# fab-slider-shield-v2_controls-only.net
KiCad netlist of a schematic drawn in EAGLE
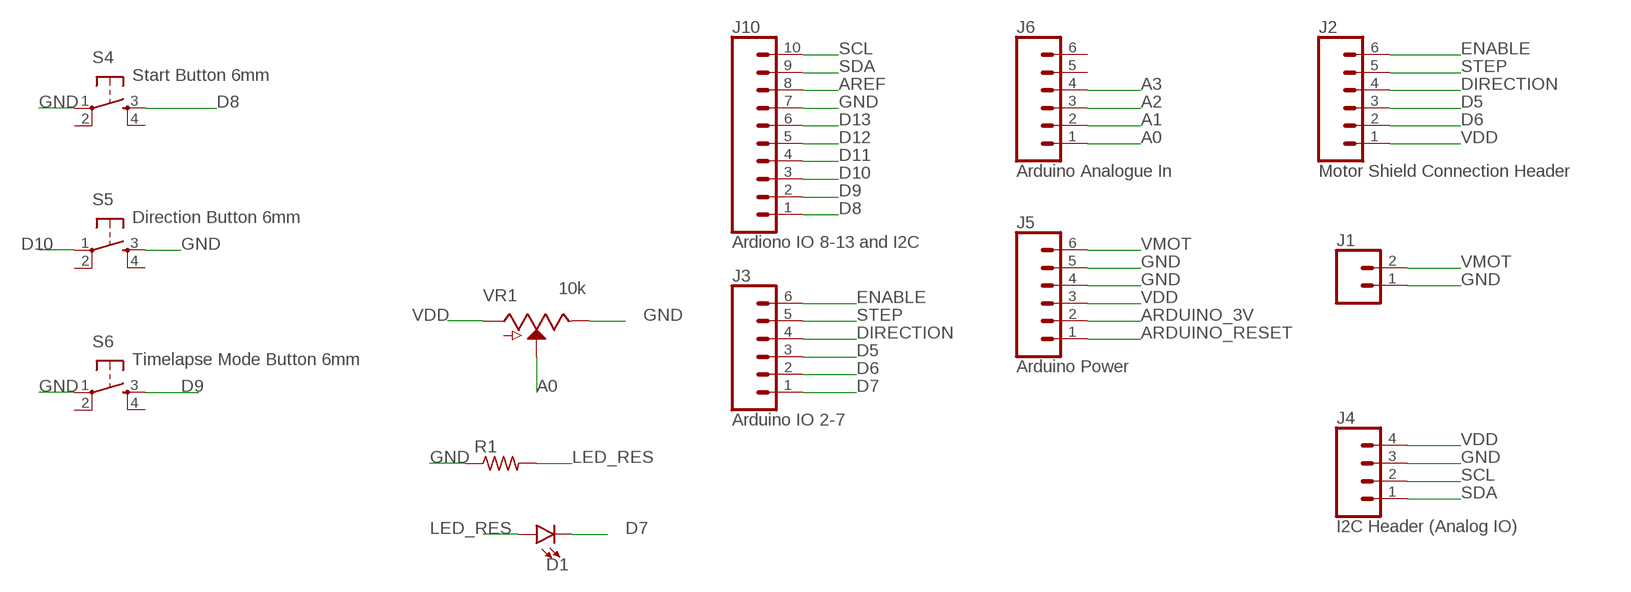
[diagram p0: schematic, sheet 1]

(export (version "E")
  (design (tool "Eeschema 10.0.6"))
  (components
    (comp (ref "D1")
      (value "LED1206")
      (footprint "eagle-import:LED-1206")
      (libsource (lib "eagle-import") (part "LED1206"))
    )
    (comp (ref "J1")
      (value "CONN_02PTH3")
      (footprint "eagle-import:1X02_LONGPADS")
      (libsource (lib "eagle-import") (part "CONN_02PTH3"))
    )
    (comp (ref "J2")
      (value "Motor Shield Connection Header")
      (footprint "eagle-import:1X06_LONGPADS")
      (libsource (lib "eagle-import") (part "CONN_06LONGPADS"))
    )
    (comp (ref "J3")
      (value "Arduino IO 2-7")
      (footprint "eagle-import:1X06_NO_SILK")
      (libsource (lib "eagle-import") (part "CONN_06NO_SILK_FEMALE_PTH"))
    )
    (comp (ref "J4")
      (value "I2C Header (Analog IO)")
      (footprint "eagle-import:1X04")
      (libsource (lib "eagle-import") (part "CONN_04"))
    )
    (comp (ref "J5")
      (value "Arduino Power")
      (footprint "eagle-import:1X06_NO_SILK")
      (libsource (lib "eagle-import") (part "CONN_06NO_SILK_FEMALE_PTH"))
    )
    (comp (ref "J6")
      (value "Arduino Analogue In")
      (footprint "eagle-import:1X06_NO_SILK")
      (libsource (lib "eagle-import") (part "CONN_06NO_SILK_FEMALE_PTH"))
    )
    (comp (ref "J10")
      (value "Ardiono IO 8-13 and I2C")
      (footprint "eagle-import:1X10_NO_SILK")
      (libsource (lib "eagle-import") (part "CONN_10NO_SILK_PTH_FEMALE"))
    )
    (comp (ref "R1")
      (value "RES-US1206FAB")
      (footprint "eagle-import:R1206FAB")
      (libsource (lib "eagle-import") (part "RES-US1206FAB"))
    )
    (comp (ref "S4")
      (value "Start Button 6mm")
      (footprint "eagle-import:6MM_SWITCH")
      (libsource (lib "eagle-import") (part "6MM_SWITCH6MM_SWITCH"))
    )
    (comp (ref "S5")
      (value "Direction Button 6mm")
      (footprint "eagle-import:6MM_SWITCH")
      (libsource (lib "eagle-import") (part "6MM_SWITCH6MM_SWITCH"))
    )
    (comp (ref "S6")
      (value "Timelapse Mode Button 6mm")
      (footprint "eagle-import:6MM_SWITCH")
      (libsource (lib "eagle-import") (part "6MM_SWITCH6MM_SWITCH"))
    )
    (comp (ref "VR1")
      (value "10k")
      (footprint "eagle-import:POT-PTH-ALPS")
      (libsource (lib "eagle-import") (part "POTENTIOMETER-PTH-9MM-1/20W-20%"))
    )
  )
  (nets
    (net (code "1") (name "/A0") (class "Default")
      (node (ref "J6") (pin "1") (pinfunction "1_1") (pintype "passive"))
      (node (ref "VR1") (pin "P$2") (pinfunction "S_P$2") (pintype "passive"))
    )
    (net (code "2") (name "/A1") (class "Default")
      (node (ref "J6") (pin "2") (pinfunction "2_2") (pintype "passive"))
    )
    (net (code "3") (name "/A2") (class "Default")
      (node (ref "J6") (pin "3") (pinfunction "3_3") (pintype "passive"))
    )
    (net (code "4") (name "/A3") (class "Default")
      (node (ref "J6") (pin "4") (pinfunction "4_4") (pintype "passive"))
    )
    (net (code "5") (name "/ARDUINO_3V") (class "Default")
      (node (ref "J5") (pin "2") (pinfunction "2_2") (pintype "passive"))
    )
    (net (code "6") (name "/ARDUINO_RESET") (class "Default")
      (node (ref "J5") (pin "1") (pinfunction "1_1") (pintype "passive"))
    )
    (net (code "7") (name "/AREF") (class "Default")
      (node (ref "J10") (pin "8") (pinfunction "8_8") (pintype "passive"))
    )
    (net (code "8") (name "/D5") (class "Default")
      (node (ref "J2") (pin "3") (pinfunction "3_3") (pintype "passive"))
      (node (ref "J3") (pin "3") (pinfunction "3_3") (pintype "passive"))
    )
    (net (code "9") (name "/D6") (class "Default")
      (node (ref "J2") (pin "2") (pinfunction "2_2") (pintype "passive"))
      (node (ref "J3") (pin "2") (pinfunction "2_2") (pintype "passive"))
    )
    (net (code "10") (name "/D7") (class "Default")
      (node (ref "D1") (pin "C") (pinfunction "C_C") (pintype "passive"))
      (node (ref "J3") (pin "1") (pinfunction "1_1") (pintype "passive"))
    )
    (net (code "11") (name "/D8") (class "Default")
      (node (ref "J10") (pin "1") (pinfunction "1_1") (pintype "passive"))
      (node (ref "S4") (pin "3") (pinfunction "S_3") (pintype "passive"))
    )
    (net (code "12") (name "/D9") (class "Default")
      (node (ref "J10") (pin "2") (pinfunction "2_2") (pintype "passive"))
      (node (ref "S6") (pin "3") (pinfunction "S_3") (pintype "passive"))
    )
    (net (code "13") (name "/D10") (class "Default")
      (node (ref "J10") (pin "3") (pinfunction "3_3") (pintype "passive"))
      (node (ref "S5") (pin "1") (pinfunction "P_1") (pintype "passive"))
    )
    (net (code "14") (name "/D11") (class "Default")
      (node (ref "J10") (pin "4") (pinfunction "4_4") (pintype "passive"))
    )
    (net (code "15") (name "/D12") (class "Default")
      (node (ref "J10") (pin "5") (pinfunction "5_5") (pintype "passive"))
    )
    (net (code "16") (name "/D13") (class "Default")
      (node (ref "J10") (pin "6") (pinfunction "6_6") (pintype "passive"))
    )
    (net (code "17") (name "/DIRECTION") (class "Default")
      (node (ref "J2") (pin "4") (pinfunction "4_4") (pintype "passive"))
      (node (ref "J3") (pin "4") (pinfunction "4_4") (pintype "passive"))
    )
    (net (code "18") (name "/ENABLE") (class "Default")
      (node (ref "J2") (pin "6") (pinfunction "6_6") (pintype "passive"))
      (node (ref "J3") (pin "6") (pinfunction "6_6") (pintype "passive"))
    )
    (net (code "19") (name "/GND") (class "Default")
      (node (ref "J1") (pin "1") (pinfunction "1_1") (pintype "passive"))
      (node (ref "J10") (pin "7") (pinfunction "7_7") (pintype "passive"))
      (node (ref "J4") (pin "3") (pinfunction "3_3") (pintype "passive"))
      (node (ref "J5") (pin "4") (pinfunction "4_4") (pintype "passive"))
      (node (ref "J5") (pin "5") (pinfunction "5_5") (pintype "passive"))
      (node (ref "R1") (pin "1") (pinfunction "1_1") (pintype "passive"))
      (node (ref "S4") (pin "1") (pinfunction "P_1") (pintype "passive"))
      (node (ref "S5") (pin "3") (pinfunction "S_3") (pintype "passive"))
      (node (ref "S6") (pin "1") (pinfunction "P_1") (pintype "passive"))
      (node (ref "VR1") (pin "P$1") (pinfunction "E_P$1") (pintype "passive"))
    )
    (net (code "20") (name "/LED_RES") (class "Default")
      (node (ref "D1") (pin "A") (pinfunction "A_A") (pintype "passive"))
      (node (ref "R1") (pin "2") (pinfunction "2_2") (pintype "passive"))
    )
    (net (code "21") (name "/SCL") (class "Default")
      (node (ref "J10") (pin "10") (pinfunction "10_10") (pintype "passive"))
      (node (ref "J4") (pin "2") (pinfunction "2_2") (pintype "passive"))
    )
    (net (code "22") (name "/SDA") (class "Default")
      (node (ref "J10") (pin "9") (pinfunction "9_9") (pintype "passive"))
      (node (ref "J4") (pin "1") (pinfunction "1_1") (pintype "passive"))
    )
    (net (code "23") (name "/STEP") (class "Default")
      (node (ref "J2") (pin "5") (pinfunction "5_5") (pintype "passive"))
      (node (ref "J3") (pin "5") (pinfunction "5_5") (pintype "passive"))
    )
    (net (code "24") (name "/VDD") (class "Default")
      (node (ref "J2") (pin "1") (pinfunction "1_1") (pintype "passive"))
      (node (ref "J4") (pin "4") (pinfunction "4_4") (pintype "passive"))
      (node (ref "J5") (pin "3") (pinfunction "3_3") (pintype "passive"))
      (node (ref "VR1") (pin "P$3") (pinfunction "A_P$3") (pintype "passive"))
    )
    (net (code "25") (name "/VMOT") (class "Default")
      (node (ref "J1") (pin "2") (pinfunction "2_2") (pintype "passive"))
      (node (ref "J5") (pin "6") (pinfunction "6_6") (pintype "passive"))
    )
    (net (code "26") (name "unconnected-(J6-Pad5)") (class "Default")
      (node (ref "J6") (pin "5") (pinfunction "5_5") (pintype "passive"))
    )
    (net (code "27") (name "unconnected-(J6-Pad6)") (class "Default")
      (node (ref "J6") (pin "6") (pinfunction "6_6") (pintype "passive"))
    )
    (net (code "28") (name "unconnected-(S4-P1-Pad2)") (class "Default")
      (node (ref "S4") (pin "2") (pinfunction "P1_2") (pintype "passive"))
    )
    (net (code "29") (name "unconnected-(S4-S1-Pad4)") (class "Default")
      (node (ref "S4") (pin "4") (pinfunction "S1_4") (pintype "passive"))
    )
    (net (code "30") (name "unconnected-(S5-P1-Pad2)") (class "Default")
      (node (ref "S5") (pin "2") (pinfunction "P1_2") (pintype "passive"))
    )
    (net (code "31") (name "unconnected-(S5-S1-Pad4)") (class "Default")
      (node (ref "S5") (pin "4") (pinfunction "S1_4") (pintype "passive"))
    )
    (net (code "32") (name "unconnected-(S6-P1-Pad2)") (class "Default")
      (node (ref "S6") (pin "2") (pinfunction "P1_2") (pintype "passive"))
    )
    (net (code "33") (name "unconnected-(S6-S1-Pad4)") (class "Default")
      (node (ref "S6") (pin "4") (pinfunction "S1_4") (pintype "passive"))
    )
  )
)
